# FX_HT32.net
KiCad netlist of a schematic drawn in Altium Designer
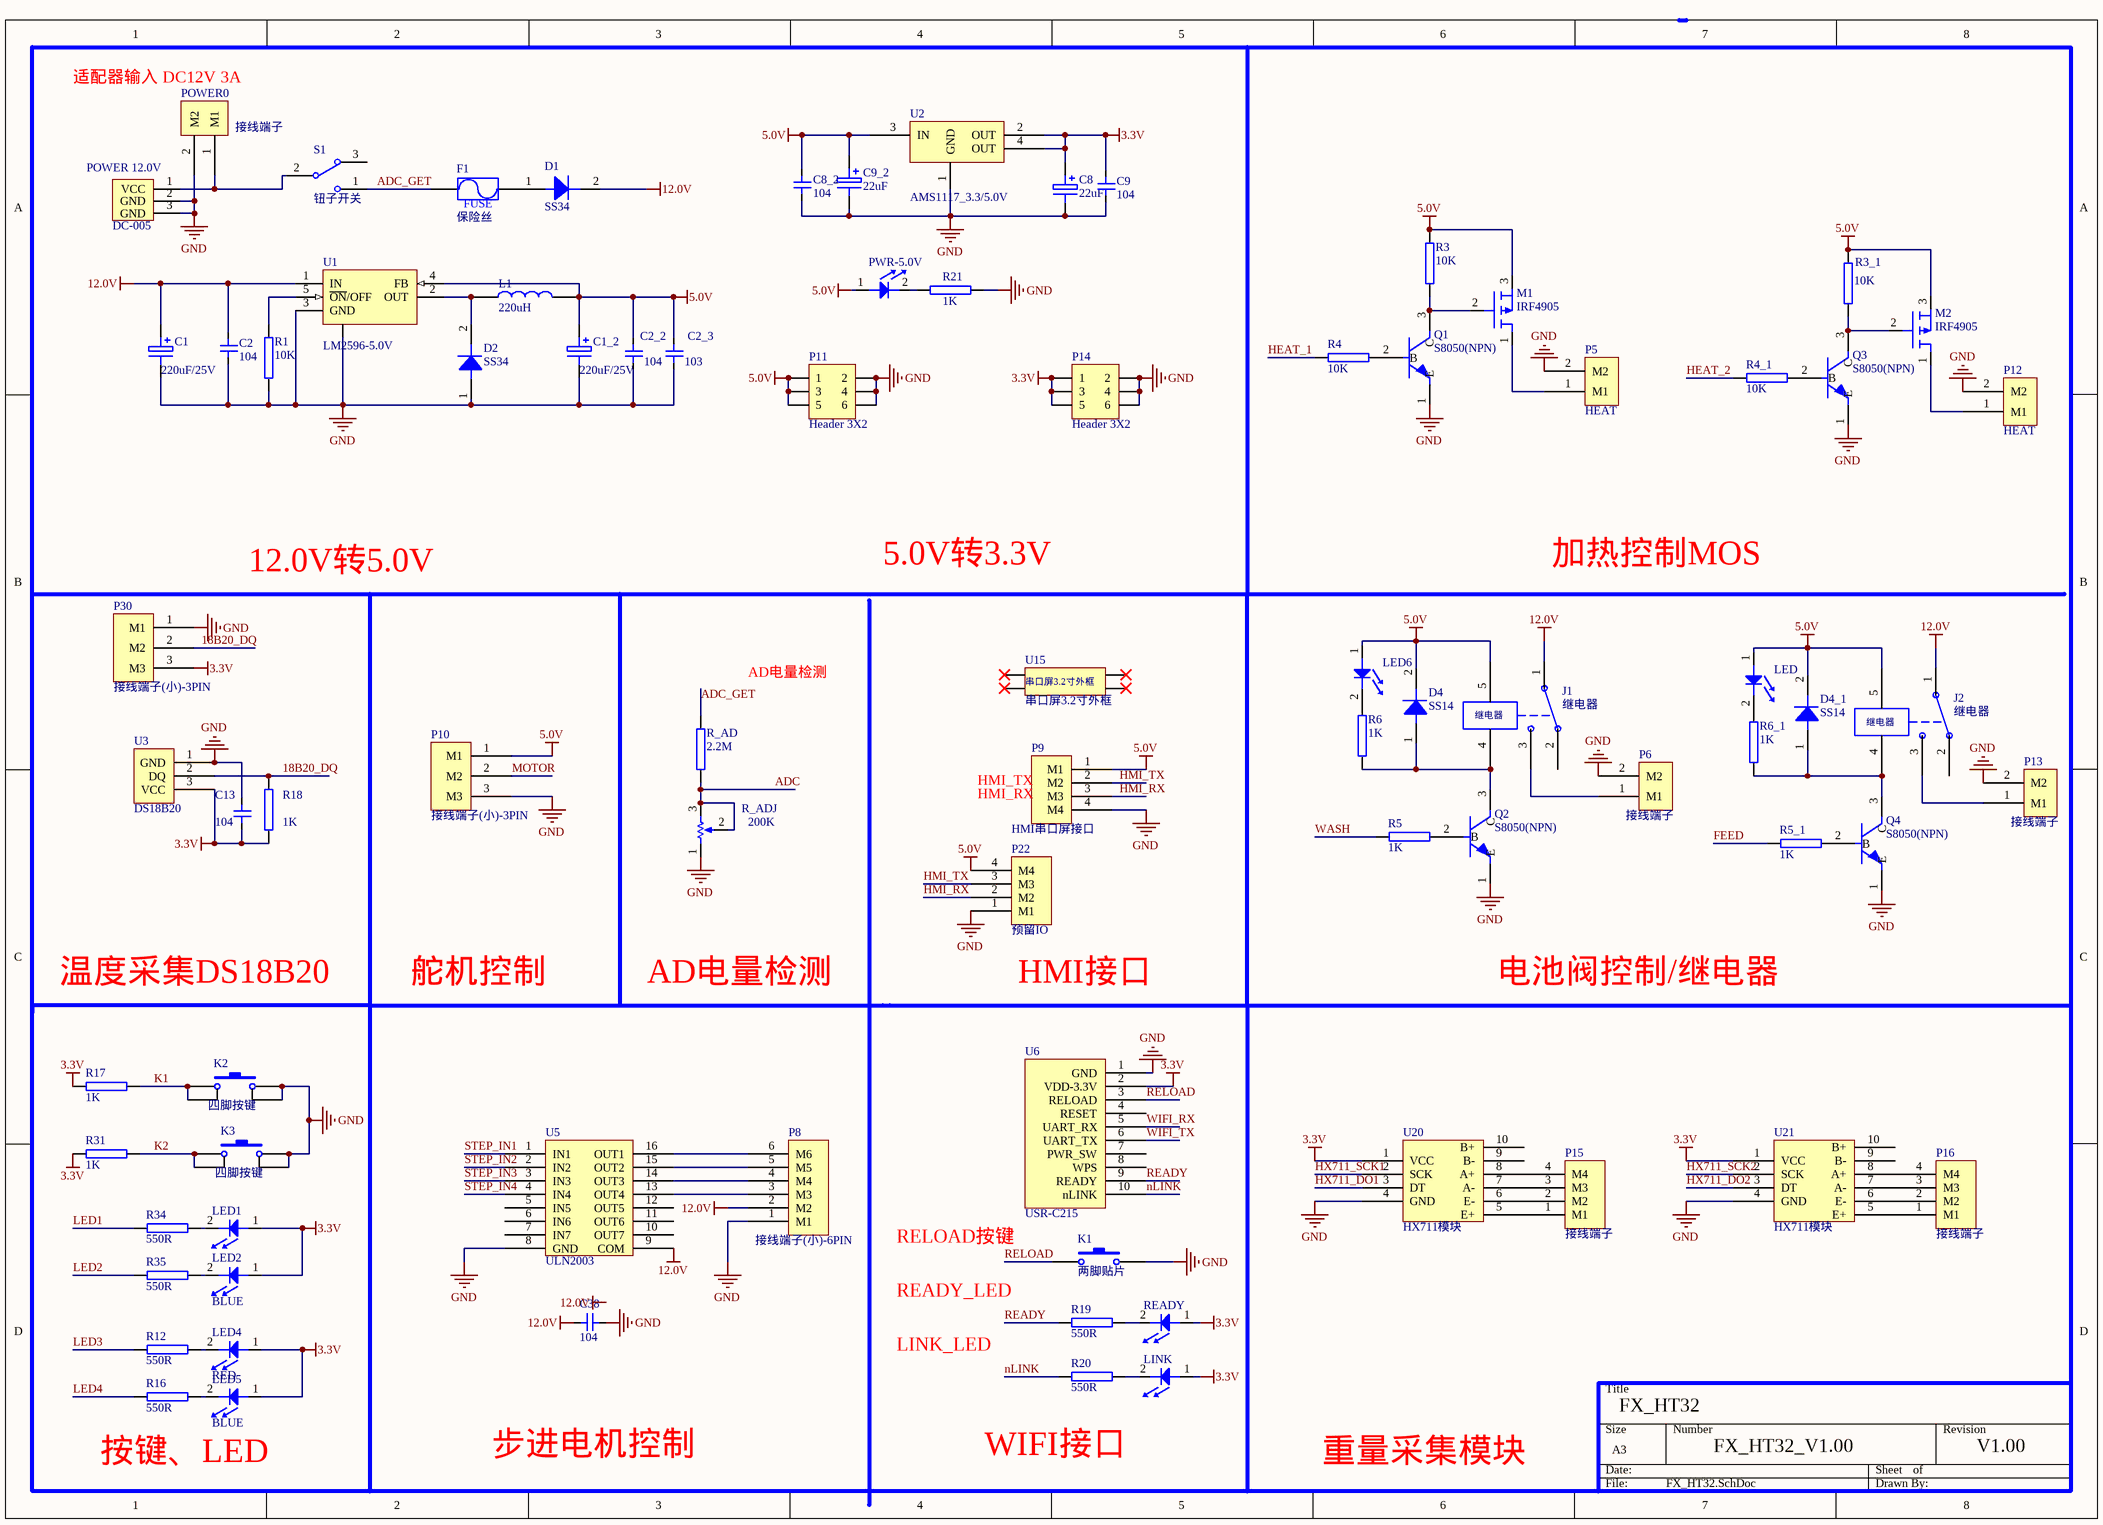
[diagram p0: FX_HT32.SchDoc]

(export (version "E")
  (design (tool "Eeschema 10.0.6"))
  (components
    (comp (ref "C1")
      (value "220uF/25V")
      (footprint "Cap1(100uF)")
      (libsource (lib "窝牛器件封装") (part "Cap1(100uF)"))
    )
    (comp (ref "C1_2")
      (value "220uF/25V")
      (footprint "Cap1(100uF)")
      (libsource (lib "窝牛器件封装") (part "Cap1(100uF)"))
    )
    (comp (ref "C2") (value "104") (footprint "0805C") (libsource (lib "窝牛器件封装") (part "C1")))
    (comp (ref "C2_2") (value "104") (footprint "0805C") (libsource (lib "窝牛器件封装") (part "C1")))
    (comp (ref "C2_3") (value "103") (footprint "0805C") (libsource (lib "窝牛器件封装") (part "C1")))
    (comp (ref "C8") (value "22uF") (footprint "Cap122uF)") (libsource (lib "窝牛器件封装") (part "Cap1(100uF)")))
    (comp (ref "C8_2") (value "104") (footprint "0805C") (libsource (lib "窝牛器件封装") (part "C1")))
    (comp (ref "C9") (value "104") (footprint "0805C") (libsource (lib "窝牛器件封装") (part "C1")))
    (comp (ref "C9_2") (value "22uF") (footprint "Cap122uF)") (libsource (lib "窝牛器件封装") (part "Cap1(100uF)")))
    (comp (ref "C13") (value "104") (footprint "0805C") (libsource (lib "窝牛器件封装") (part "C1")))
    (comp (ref "C38") (value "104") (footprint "0805C") (libsource (lib "窝牛器件封装") (part "C1")))
    (comp (ref "D1") (value "SS34") (footprint "SS14") (libsource (lib "窝牛器件封装") (part "SS14")))
    (comp (ref "D2") (value "SS34") (footprint "SS14") (libsource (lib "窝牛器件封装") (part "SS14")))
    (comp (ref "D4") (value "SS14") (footprint "SS14") (libsource (lib "窝牛器件封装") (part "SS14")))
    (comp (ref "D4_1") (value "SS14") (footprint "SS14") (libsource (lib "窝牛器件封装") (part "SS14")))
    (comp (ref "F1") (value "保险丝") (footprint "1812") (libsource (lib "窝牛器件封装") (part "F1")))
    (comp (ref "J1") (value "继电器") (footprint "继电器") (libsource (lib "窝牛器件封装") (part "继电器")))
    (comp (ref "J2") (value "继电器") (footprint "继电器") (libsource (lib "窝牛器件封装") (part "继电器")))
    (comp (ref "K1") (value "两脚贴片") (footprint "贴片按键") (libsource (lib "窝牛器件封装") (part "Key(两脚贴片)")))
    (comp (ref "K2") (value "四脚按键") (footprint "SW_PB4_DIP") (libsource (lib "窝牛器件封装") (part "Key(四脚)")))
    (comp (ref "K3") (value "四脚按键") (footprint "SW_PB4_DIP") (libsource (lib "窝牛器件封装") (part "Key(四脚)")))
    (comp (ref "L1") (value "220uH") (footprint "电感 220uh") (libsource (lib "窝牛器件封装") (part "L1")))
    (comp (ref "LED") (value "~") (footprint "0805LED") (libsource (lib "窝牛器件封装") (part "LED")))
    (comp (ref "LED1") (value "~") (footprint "0805LED") (libsource (lib "窝牛器件封装") (part "LED")))
    (comp (ref "LED2") (value "BLUE") (footprint "0805LED") (libsource (lib "窝牛器件封装") (part "LED")))
    (comp (ref "LED4") (value "RED") (footprint "0805LED") (libsource (lib "窝牛器件封装") (part "LED")))
    (comp (ref "LED5") (value "BLUE") (footprint "0805LED") (libsource (lib "窝牛器件封装") (part "LED")))
    (comp (ref "LED6") (value "~") (footprint "0805LED") (libsource (lib "窝牛器件封装") (part "LED")))
    (comp (ref "LINK") (value "~") (footprint "0805LED") (libsource (lib "") (part "LED_1")))
    (comp (ref "M1") (value "IRF4905") (footprint "IRF4905") (libsource (lib "窝牛器件封装") (part "IRF4905")))
    (comp (ref "M2") (value "IRF4905") (footprint "IRF4905") (libsource (lib "窝牛器件封装") (part "IRF4905")))
    (comp (ref "P5") (value "HEAT") (footprint "HEAT") (libsource (lib "窝牛器件封装") (part "接线端子(小)-2PIN")))
    (comp (ref "P6")
      (value "接线端子")
      (footprint "接线端子(小)-2PIN")
      (libsource (lib "窝牛器件封装") (part "接线端子(小)-2PIN"))
    )
    (comp (ref "P8")
      (value "接线端子(小)-6PIN")
      (footprint "接线端子(小)-6PIN")
      (libsource (lib "窝牛器件封装") (part "接线端子(小)-6PIN"))
    )
    (comp (ref "P9")
      (value "HMI串口屏接口")
      (footprint "接线端子(小)-4PIN")
      (libsource (lib "窝牛器件封装") (part "接线端子(小)-4PIN"))
    )
    (comp (ref "P10")
      (value "接线端子(小)-3PIN")
      (footprint "接线端子(小)-3PIN")
      (libsource (lib "窝牛器件封装") (part "接线端子(小)-3PIN"))
    )
    (comp (ref "P11")
      (value "Header 3X2")
      (footprint "Header 3X2")
      (libsource (lib "窝牛器件封装") (part "Header 3X2"))
    )
    (comp (ref "P12") (value "HEAT") (footprint "HEAT") (libsource (lib "窝牛器件封装") (part "接线端子(小)-2PIN")))
    (comp (ref "P13")
      (value "接线端子")
      (footprint "接线端子(小)-2PIN")
      (libsource (lib "窝牛器件封装") (part "接线端子(小)-2PIN"))
    )
    (comp (ref "P14")
      (value "Header 3X2")
      (footprint "Header 3X2")
      (libsource (lib "窝牛器件封装") (part "Header 3X2"))
    )
    (comp (ref "P15") (value "接线端子") (footprint "接线端子(小)-4PIN") (libsource (lib "") (part "接线端子(小)-4PIN_1")))
    (comp (ref "P16") (value "接线端子") (footprint "接线端子(小)-4PIN") (libsource (lib "") (part "接线端子(小)-4PIN_1")))
    (comp (ref "P22") (value "预留IO") (footprint "接线端子(小)-4PIN") (libsource (lib "") (part "接线端子(小)-4PIN_1")))
    (comp (ref "P30")
      (value "接线端子(小)-3PIN")
      (footprint "接线端子(小)-3PIN")
      (libsource (lib "窝牛器件封装") (part "接线端子(小)-3PIN"))
    )
    (comp (ref "POWER 12.0V")
      (value "DC-005")
      (footprint "DC-005")
      (libsource (lib "窝牛器件封装") (part "DC-005"))
    )
    (comp (ref "POWER0") (value "接线端子") (footprint "HEAT") (libsource (lib "") (part "接线端子(小)-2PIN_1")))
    (comp (ref "PWR-5.0V") (value "~") (footprint "0805LED") (libsource (lib "") (part "LED_1")))
    (comp (ref "Q1") (value "S8050(NPN)") (footprint "NPN") (libsource (lib "窝牛器件封装") (part "Q2")))
    (comp (ref "Q2") (value "S8050(NPN)") (footprint "NPN") (libsource (lib "窝牛器件封装") (part "Q2")))
    (comp (ref "Q3") (value "S8050(NPN)") (footprint "NPN") (libsource (lib "窝牛器件封装") (part "Q2")))
    (comp (ref "Q4") (value "S8050(NPN)") (footprint "NPN") (libsource (lib "窝牛器件封装") (part "Q2")))
    (comp (ref "R1") (value "10K") (footprint "0805R") (libsource (lib "窝牛器件封装") (part "R1")))
    (comp (ref "R3") (value "10K") (footprint "0805R") (libsource (lib "窝牛器件封装") (part "R1")))
    (comp (ref "R3_1") (value "10K") (footprint "0805R") (libsource (lib "窝牛器件封装") (part "R1")))
    (comp (ref "R4") (value "10K") (footprint "0805R") (libsource (lib "窝牛器件封装") (part "R1")))
    (comp (ref "R4_1") (value "10K") (footprint "0805R") (libsource (lib "窝牛器件封装") (part "R1")))
    (comp (ref "R5") (value "1K") (footprint "0805R") (libsource (lib "窝牛器件封装") (part "R1")))
    (comp (ref "R5_1") (value "1K") (footprint "0805R") (libsource (lib "窝牛器件封装") (part "R1")))
    (comp (ref "R6") (value "1K") (footprint "0805R") (libsource (lib "窝牛器件封装") (part "R1")))
    (comp (ref "R6_1") (value "1K") (footprint "0805R") (libsource (lib "窝牛器件封装") (part "R1")))
    (comp (ref "R12") (value "550R") (footprint "0805R") (libsource (lib "窝牛器件封装") (part "R1")))
    (comp (ref "R16") (value "550R") (footprint "0805R") (libsource (lib "窝牛器件封装") (part "R1")))
    (comp (ref "R17") (value "1K") (footprint "0805R") (libsource (lib "窝牛器件封装") (part "R1")))
    (comp (ref "R18") (value "1K") (footprint "0805R") (libsource (lib "窝牛器件封装") (part "R1")))
    (comp (ref "R19") (value "550R") (footprint "0805R") (libsource (lib "窝牛器件封装") (part "R1")))
    (comp (ref "R20") (value "550R") (footprint "0805R") (libsource (lib "窝牛器件封装") (part "R1")))
    (comp (ref "R21") (value "1K") (footprint "0805R") (libsource (lib "窝牛器件封装") (part "R1")))
    (comp (ref "R31") (value "1K") (footprint "0805R") (libsource (lib "窝牛器件封装") (part "R1")))
    (comp (ref "R34") (value "550R") (footprint "0805R") (libsource (lib "窝牛器件封装") (part "R1")))
    (comp (ref "R35") (value "550R") (footprint "0805R") (libsource (lib "窝牛器件封装") (part "R1")))
    (comp (ref "READY") (value "~") (footprint "0805LED") (libsource (lib "") (part "LED_1")))
    (comp (ref "R_AD") (value "2.2M") (footprint "0805R") (libsource (lib "窝牛器件封装") (part "R1")))
    (comp (ref "R_ADJ") (value "200K") (footprint "电位器") (libsource (lib "窝牛器件封装") (part "RPot")))
    (comp (ref "S1") (value "钮子开关") (footprint "钮子开关(大)") (libsource (lib "窝牛器件封装") (part "钮子开关")))
    (comp (ref "U1") (value "LM2596-5.0V") (footprint "TO-263-5") (libsource (lib "窝牛器件封装") (part "LM2596")))
    (comp (ref "U2")
      (value "AMS1117_3.3/5.0V")
      (footprint "SOT-223")
      (libsource (lib "窝牛器件封装") (part "AMS1117-3.3V/5.0V"))
    )
    (comp (ref "U3") (value "DS18B20") (footprint "DS18B20") (libsource (lib "窝牛器件封装") (part "DS18B20")))
    (comp (ref "U5") (value "ULN2003") (footprint "ULN2003") (libsource (lib "窝牛器件封装") (part "ULN2003")))
    (comp (ref "U6") (value "USR-C215") (footprint "USR-C215") (libsource (lib "窝牛器件封装") (part "USR-C215")))
    (comp (ref "U15") (value "串口屏3.2寸外框") (footprint "串口屏 3.2寸") (libsource (lib "窝牛器件封装") (part "串口屏3.2寸")))
    (comp (ref "U20") (value "HX711模块") (footprint "HX711模块") (libsource (lib "窝牛器件封装") (part "HX711模块")))
    (comp (ref "U21") (value "HX711模块") (footprint "HX711模块") (libsource (lib "窝牛器件封装") (part "HX711模块")))
  )
  (nets
    (net (code "1") (name "/18B20_DQ") (class "Default")
      (node (ref "P30") (pin "2") (pinfunction "M2_2") (pintype "passive"))
      (node (ref "R18") (pin "1") (pinfunction "1_1") (pintype "passive"))
      (node (ref "U3") (pin "2") (pinfunction "DQ_2") (pintype "passive"))
    )
    (net (code "2") (name "/ADC") (class "Default")
      (node (ref "R_AD") (pin "2") (pinfunction "2_2") (pintype "passive"))
      (node (ref "R_ADJ") (pin "2") (pinfunction "TAP_2") (pintype "passive"))
      (node (ref "R_ADJ") (pin "3") (pinfunction "BOT_3") (pintype "passive"))
    )
    (net (code "3") (name "/ADC_GET") (class "Default")
      (node (ref "F1") (pin "1") (pinfunction "1_1") (pintype "passive"))
      (node (ref "R_AD") (pin "1") (pinfunction "1_1") (pintype "passive"))
      (node (ref "S1") (pin "1") (pinfunction "1_1") (pintype "passive"))
    )
    (net (code "4") (name "/FEED") (class "Default")
      (node (ref "R5_1") (pin "1") (pinfunction "1_1") (pintype "passive"))
    )
    (net (code "5") (name "/HEAT_1") (class "Default")
      (node (ref "R4") (pin "1") (pinfunction "1_1") (pintype "passive"))
    )
    (net (code "6") (name "/HEAT_2") (class "Default")
      (node (ref "R4_1") (pin "1") (pinfunction "1_1") (pintype "passive"))
    )
    (net (code "7") (name "/HMI_RX") (class "Default")
      (node (ref "P22") (pin "2") (pinfunction "M2_2") (pintype "passive"))
      (node (ref "P9") (pin "3") (pinfunction "M3_3") (pintype "passive"))
    )
    (net (code "8") (name "/HMI_TX") (class "Default")
      (node (ref "P22") (pin "3") (pinfunction "M3_3") (pintype "passive"))
      (node (ref "P9") (pin "2") (pinfunction "M2_2") (pintype "passive"))
    )
    (net (code "9") (name "/HX711_DO1") (class "Default")
      (node (ref "U20") (pin "3") (pinfunction "DT_3") (pintype "passive"))
    )
    (net (code "10") (name "/HX711_DO2") (class "Default")
      (node (ref "U21") (pin "3") (pinfunction "DT_3") (pintype "passive"))
    )
    (net (code "11") (name "/HX711_SCK1") (class "Default")
      (node (ref "U20") (pin "2") (pinfunction "SCK_2") (pintype "passive"))
    )
    (net (code "12") (name "/HX711_SCK2") (class "Default")
      (node (ref "U21") (pin "2") (pinfunction "SCK_2") (pintype "passive"))
    )
    (net (code "13") (name "/K1") (class "Default")
      (node (ref "K2") (pin "1") (pinfunction "1_1") (pintype "passive"))
      (node (ref "K2") (pin "4") (pinfunction "4_4") (pintype "passive"))
      (node (ref "R17") (pin "2") (pinfunction "2_2") (pintype "passive"))
    )
    (net (code "14") (name "/K2") (class "Default")
      (node (ref "K3") (pin "1") (pinfunction "1_1") (pintype "passive"))
      (node (ref "K3") (pin "4") (pinfunction "4_4") (pintype "passive"))
      (node (ref "R31") (pin "2") (pinfunction "2_2") (pintype "passive"))
    )
    (net (code "15") (name "/LED1") (class "Default")
      (node (ref "R34") (pin "1") (pinfunction "1_1") (pintype "passive"))
    )
    (net (code "16") (name "/LED2") (class "Default")
      (node (ref "R35") (pin "1") (pinfunction "1_1") (pintype "passive"))
    )
    (net (code "17") (name "/LED3") (class "Default")
      (node (ref "R12") (pin "1") (pinfunction "1_1") (pintype "passive"))
    )
    (net (code "18") (name "/LED4") (class "Default")
      (node (ref "R16") (pin "1") (pinfunction "1_1") (pintype "passive"))
    )
    (net (code "19") (name "/MOTOR") (class "Default")
      (node (ref "P10") (pin "2") (pinfunction "M2_2") (pintype "passive"))
    )
    (net (code "20") (name "/READY") (class "Default")
      (node (ref "R19") (pin "1") (pinfunction "1_1") (pintype "passive"))
      (node (ref "U6") (pin "9") (pinfunction "READY_9") (pintype "passive"))
    )
    (net (code "21") (name "/RELOAD") (class "Default")
      (node (ref "K1") (pin "1") (pinfunction "1_1") (pintype "passive"))
      (node (ref "U6") (pin "3") (pinfunction "RELOAD_3") (pintype "passive"))
    )
    (net (code "22") (name "/STEP_IN1") (class "Default")
      (node (ref "U5") (pin "1") (pinfunction "IN1_1") (pintype "passive"))
    )
    (net (code "23") (name "/STEP_IN2") (class "Default")
      (node (ref "U5") (pin "2") (pinfunction "IN2_2") (pintype "passive"))
    )
    (net (code "24") (name "/STEP_IN3") (class "Default")
      (node (ref "U5") (pin "3") (pinfunction "IN3_3") (pintype "passive"))
    )
    (net (code "25") (name "/STEP_IN4") (class "Default")
      (node (ref "U5") (pin "4") (pinfunction "IN4_4") (pintype "passive"))
    )
    (net (code "26") (name "/WASH") (class "Default")
      (node (ref "R5") (pin "1") (pinfunction "1_1") (pintype "passive"))
    )
    (net (code "27") (name "/WIFI_RX") (class "Default")
      (node (ref "U6") (pin "5") (pinfunction "UART_RX_5") (pintype "passive"))
    )
    (net (code "28") (name "/WIFI_TX") (class "Default")
      (node (ref "U6") (pin "6") (pinfunction "UART_TX_6") (pintype "passive"))
    )
    (net (code "29") (name "/nLINK") (class "Default")
      (node (ref "R20") (pin "1") (pinfunction "1_1") (pintype "passive"))
      (node (ref "U6") (pin "10") (pinfunction "nLINK_10") (pintype "passive"))
    )
    (net (code "30") (name "3.3V") (class "Default")
      (node (ref "C13") (pin "1") (pinfunction "1_1") (pintype "passive"))
      (node (ref "C8") (pin "1") (pinfunction "1_1") (pintype "passive"))
      (node (ref "C9") (pin "2") (pinfunction "2_2") (pintype "passive"))
      (node (ref "LED1") (pin "1") (pinfunction "1_1") (pintype "passive"))
      (node (ref "LED2") (pin "1") (pinfunction "1_1") (pintype "passive"))
      (node (ref "LED4") (pin "1") (pinfunction "1_1") (pintype "passive"))
      (node (ref "LED5") (pin "1") (pinfunction "1_1") (pintype "passive"))
      (node (ref "LINK") (pin "1") (pinfunction "1_1") (pintype "passive"))
      (node (ref "P14") (pin "1") (pinfunction "1_1") (pintype "passive"))
      (node (ref "P14") (pin "3") (pinfunction "3_3") (pintype "passive"))
      (node (ref "P14") (pin "5") (pinfunction "5_5") (pintype "passive"))
      (node (ref "P30") (pin "3") (pinfunction "M3_3") (pintype "passive"))
      (node (ref "R17") (pin "1") (pinfunction "1_1") (pintype "passive"))
      (node (ref "R18") (pin "2") (pinfunction "2_2") (pintype "passive"))
      (node (ref "R31") (pin "1") (pinfunction "1_1") (pintype "passive"))
      (node (ref "READY") (pin "1") (pinfunction "1_1") (pintype "passive"))
      (node (ref "U2") (pin "2") (pinfunction "OUT_2") (pintype "passive"))
      (node (ref "U2") (pin "4") (pinfunction "OUT_4") (pintype "passive"))
      (node (ref "U20") (pin "1") (pinfunction "VCC_1") (pintype "passive"))
      (node (ref "U21") (pin "1") (pinfunction "VCC_1") (pintype "passive"))
      (node (ref "U3") (pin "3") (pinfunction "VCC_3") (pintype "passive"))
      (node (ref "U6") (pin "2") (pinfunction "VDD-3.3V_2") (pintype "passive"))
    )
    (net (code "31") (name "5.0V") (class "Default")
      (node (ref "C1_2") (pin "1") (pinfunction "1_1") (pintype "passive"))
      (node (ref "C2_2") (pin "2") (pinfunction "2_2") (pintype "passive"))
      (node (ref "C2_3") (pin "2") (pinfunction "2_2") (pintype "passive"))
      (node (ref "C8_2") (pin "2") (pinfunction "2_2") (pintype "passive"))
      (node (ref "C9_2") (pin "1") (pinfunction "1_1") (pintype "passive"))
      (node (ref "D4") (pin "2") (pinfunction "2_2") (pintype "passive"))
      (node (ref "D4_1") (pin "2") (pinfunction "2_2") (pintype "passive"))
      (node (ref "J1") (pin "5") (pinfunction "5_5") (pintype "passive"))
      (node (ref "J2") (pin "5") (pinfunction "5_5") (pintype "passive"))
      (node (ref "L1") (pin "2") (pinfunction "2_2") (pintype "passive"))
      (node (ref "LED") (pin "1") (pinfunction "1_1") (pintype "passive"))
      (node (ref "LED6") (pin "1") (pinfunction "1_1") (pintype "passive"))
      (node (ref "M1") (pin "3") (pinfunction "3_3") (pintype "passive"))
      (node (ref "M2") (pin "3") (pinfunction "3_3") (pintype "passive"))
      (node (ref "P10") (pin "1") (pinfunction "M1_1") (pintype "passive"))
      (node (ref "P11") (pin "1") (pinfunction "1_1") (pintype "passive"))
      (node (ref "P11") (pin "3") (pinfunction "3_3") (pintype "passive"))
      (node (ref "P11") (pin "5") (pinfunction "5_5") (pintype "passive"))
      (node (ref "P22") (pin "4") (pinfunction "M4_4") (pintype "passive"))
      (node (ref "P9") (pin "1") (pinfunction "M1_1") (pintype "passive"))
      (node (ref "PWR-5.0V") (pin "1") (pinfunction "1_1") (pintype "passive"))
      (node (ref "R3") (pin "2") (pinfunction "2_2") (pintype "passive"))
      (node (ref "R3_1") (pin "2") (pinfunction "2_2") (pintype "passive"))
      (node (ref "U1") (pin "4") (pinfunction "FB_4") (pintype "input"))
      (node (ref "U2") (pin "3") (pinfunction "IN_3") (pintype "passive"))
    )
    (net (code "32") (name "12.0V") (class "Default")
      (node (ref "C1") (pin "1") (pinfunction "1_1") (pintype "passive"))
      (node (ref "C2") (pin "2") (pinfunction "2_2") (pintype "passive"))
      (node (ref "C38") (pin "2") (pinfunction "2_2") (pintype "passive"))
      (node (ref "D1") (pin "2") (pinfunction "2_2") (pintype "passive"))
      (node (ref "J1") (pin "1") (pinfunction "1_1") (pintype "passive"))
      (node (ref "J2") (pin "1") (pinfunction "1_1") (pintype "passive"))
      (node (ref "P8") (pin "2") (pinfunction "M2_2") (pintype "passive"))
      (node (ref "U1") (pin "1") (pinfunction "IN_1") (pintype "power_in"))
      (node (ref "U5") (pin "9") (pinfunction "COM_9") (pintype "passive"))
    )
    (net (code "33") (name "GND") (class "Default")
      (node (ref "C1") (pin "2") (pinfunction "2_2") (pintype "passive"))
      (node (ref "C13") (pin "2") (pinfunction "2_2") (pintype "passive"))
      (node (ref "C1_2") (pin "2") (pinfunction "2_2") (pintype "passive"))
      (node (ref "C2") (pin "1") (pinfunction "1_1") (pintype "passive"))
      (node (ref "C2_2") (pin "1") (pinfunction "1_1") (pintype "passive"))
      (node (ref "C2_3") (pin "1") (pinfunction "1_1") (pintype "passive"))
      (node (ref "C38") (pin "1") (pinfunction "1_1") (pintype "passive"))
      (node (ref "C8") (pin "2") (pinfunction "2_2") (pintype "passive"))
      (node (ref "C8_2") (pin "1") (pinfunction "1_1") (pintype "passive"))
      (node (ref "C9") (pin "1") (pinfunction "1_1") (pintype "passive"))
      (node (ref "C9_2") (pin "2") (pinfunction "2_2") (pintype "passive"))
      (node (ref "D2") (pin "1") (pintype "passive"))
      (node (ref "K1") (pin "2") (pinfunction "2_2") (pintype "passive"))
      (node (ref "K2") (pin "2") (pinfunction "2_2") (pintype "passive"))
      (node (ref "K2") (pin "3") (pinfunction "3_3") (pintype "passive"))
      (node (ref "K3") (pin "2") (pinfunction "2_2") (pintype "passive"))
      (node (ref "K3") (pin "3") (pinfunction "3_3") (pintype "passive"))
      (node (ref "P10") (pin "3") (pinfunction "M3_3") (pintype "passive"))
      (node (ref "P11") (pin "2") (pinfunction "2_2") (pintype "passive"))
      (node (ref "P11") (pin "4") (pinfunction "4_4") (pintype "passive"))
      (node (ref "P11") (pin "6") (pinfunction "6_6") (pintype "passive"))
      (node (ref "P12") (pin "2") (pinfunction "M2_2") (pintype "passive"))
      (node (ref "P13") (pin "2") (pinfunction "M2_2") (pintype "passive"))
      (node (ref "P14") (pin "2") (pinfunction "2_2") (pintype "passive"))
      (node (ref "P14") (pin "4") (pinfunction "4_4") (pintype "passive"))
      (node (ref "P14") (pin "6") (pinfunction "6_6") (pintype "passive"))
      (node (ref "P22") (pin "1") (pinfunction "M1_1") (pintype "passive"))
      (node (ref "P30") (pin "1") (pinfunction "M1_1") (pintype "passive"))
      (node (ref "P5") (pin "2") (pinfunction "M2_2") (pintype "passive"))
      (node (ref "P6") (pin "2") (pinfunction "M2_2") (pintype "passive"))
      (node (ref "P8") (pin "1") (pinfunction "M1_1") (pintype "passive"))
      (node (ref "P9") (pin "4") (pinfunction "M4_4") (pintype "passive"))
      (node (ref "POWER 12.0V") (pin "2") (pinfunction "GND_2") (pintype "passive"))
      (node (ref "POWER 12.0V") (pin "3") (pinfunction "GND_3") (pintype "passive"))
      (node (ref "POWER0") (pin "2") (pinfunction "M2_2") (pintype "passive"))
      (node (ref "Q1") (pin "1") (pinfunction "E_1") (pintype "passive"))
      (node (ref "Q2") (pin "1") (pinfunction "E_1") (pintype "passive"))
      (node (ref "Q3") (pin "1") (pinfunction "E_1") (pintype "passive"))
      (node (ref "Q4") (pin "1") (pinfunction "E_1") (pintype "passive"))
      (node (ref "R1") (pin "1") (pinfunction "1_1") (pintype "passive"))
      (node (ref "R21") (pin "2") (pinfunction "2_2") (pintype "passive"))
      (node (ref "R_ADJ") (pin "1") (pinfunction "TOP_1") (pintype "passive"))
      (node (ref "U1") (pin "3") (pinfunction "GND_3") (pintype "power_in"))
      (node (ref "U1") (pin "6") (pinfunction "6_6") (pintype "power_in"))
      (node (ref "U2") (pin "1") (pinfunction "GND_1") (pintype "passive"))
      (node (ref "U20") (pin "4") (pinfunction "GND_4") (pintype "passive"))
      (node (ref "U21") (pin "4") (pinfunction "GND_4") (pintype "passive"))
      (node (ref "U3") (pin "1") (pinfunction "GND_1") (pintype "passive"))
      (node (ref "U5") (pin "8") (pinfunction "GND_8") (pintype "passive"))
      (node (ref "U6") (pin "1") (pinfunction "GND_1") (pintype "passive"))
    )
    (net (code "34") (name "Net-(D1-Pad1)") (class "Default")
      (node (ref "D1") (pin "1") (pintype "passive"))
      (node (ref "F1") (pin "2") (pinfunction "2_2") (pintype "passive"))
    )
    (net (code "35") (name "Net-(LED-Pad2)") (class "Default")
      (node (ref "LED") (pin "2") (pinfunction "2_2") (pintype "passive"))
      (node (ref "R6_1") (pin "1") (pinfunction "1_1") (pintype "passive"))
    )
    (net (code "36") (name "Net-(LED1-Pad2)") (class "Default")
      (node (ref "LED1") (pin "2") (pinfunction "2_2") (pintype "passive"))
      (node (ref "R34") (pin "2") (pinfunction "2_2") (pintype "passive"))
    )
    (net (code "37") (name "Net-(LED2-Pad2)") (class "Default")
      (node (ref "LED2") (pin "2") (pinfunction "2_2") (pintype "passive"))
      (node (ref "R35") (pin "2") (pinfunction "2_2") (pintype "passive"))
    )
    (net (code "38") (name "Net-(LED4-Pad2)") (class "Default")
      (node (ref "LED4") (pin "2") (pinfunction "2_2") (pintype "passive"))
      (node (ref "R12") (pin "2") (pinfunction "2_2") (pintype "passive"))
    )
    (net (code "39") (name "Net-(LED5-Pad2)") (class "Default")
      (node (ref "LED5") (pin "2") (pinfunction "2_2") (pintype "passive"))
      (node (ref "R16") (pin "2") (pinfunction "2_2") (pintype "passive"))
    )
    (net (code "40") (name "Net-(LED6-Pad2)") (class "Default")
      (node (ref "LED6") (pin "2") (pinfunction "2_2") (pintype "passive"))
      (node (ref "R6") (pin "1") (pinfunction "1_1") (pintype "passive"))
    )
    (net (code "41") (name "Net-(LINK-Pad2)") (class "Default")
      (node (ref "LINK") (pin "2") (pinfunction "2_2") (pintype "passive"))
      (node (ref "R20") (pin "2") (pinfunction "2_2") (pintype "passive"))
    )
    (net (code "42") (name "Net-(P5-M1)") (class "Default")
      (node (ref "M1") (pin "1") (pinfunction "1_1") (pintype "passive"))
      (node (ref "P5") (pin "1") (pinfunction "M1_1") (pintype "passive"))
    )
    (net (code "43") (name "Net-(P6-M1)") (class "Default")
      (node (ref "J1") (pin "3") (pinfunction "3_3") (pintype "passive"))
      (node (ref "P6") (pin "1") (pinfunction "M1_1") (pintype "passive"))
    )
    (net (code "44") (name "Net-(P8-M3)") (class "Default")
      (node (ref "P8") (pin "3") (pinfunction "M3_3") (pintype "passive"))
      (node (ref "U5") (pin "13") (pinfunction "OUT4_13") (pintype "passive"))
    )
    (net (code "45") (name "Net-(P8-M4)") (class "Default")
      (node (ref "P8") (pin "4") (pinfunction "M4_4") (pintype "passive"))
      (node (ref "U5") (pin "14") (pinfunction "OUT3_14") (pintype "passive"))
    )
    (net (code "46") (name "Net-(P8-M5)") (class "Default")
      (node (ref "P8") (pin "5") (pinfunction "M5_5") (pintype "passive"))
      (node (ref "U5") (pin "15") (pinfunction "OUT2_15") (pintype "passive"))
    )
    (net (code "47") (name "Net-(P8-M6)") (class "Default")
      (node (ref "P8") (pin "6") (pinfunction "M6_6") (pintype "passive"))
      (node (ref "U5") (pin "16") (pinfunction "OUT1_16") (pintype "passive"))
    )
    (net (code "48") (name "Net-(P12-M1)") (class "Default")
      (node (ref "M2") (pin "1") (pinfunction "1_1") (pintype "passive"))
      (node (ref "P12") (pin "1") (pinfunction "M1_1") (pintype "passive"))
    )
    (net (code "49") (name "Net-(P13-M1)") (class "Default")
      (node (ref "J2") (pin "3") (pinfunction "3_3") (pintype "passive"))
      (node (ref "P13") (pin "1") (pinfunction "M1_1") (pintype "passive"))
    )
    (net (code "50") (name "Net-(P15-M1)") (class "Default")
      (node (ref "P15") (pin "1") (pinfunction "M1_1") (pintype "passive"))
      (node (ref "U20") (pin "5") (pinfunction "E+_5") (pintype "passive"))
    )
    (net (code "51") (name "Net-(P15-M2)") (class "Default")
      (node (ref "P15") (pin "2") (pinfunction "M2_2") (pintype "passive"))
      (node (ref "U20") (pin "6") (pinfunction "E-_6") (pintype "passive"))
    )
    (net (code "52") (name "Net-(P15-M3)") (class "Default")
      (node (ref "P15") (pin "3") (pinfunction "M3_3") (pintype "passive"))
      (node (ref "U20") (pin "7") (pinfunction "A-_7") (pintype "passive"))
    )
    (net (code "53") (name "Net-(P15-M4)") (class "Default")
      (node (ref "P15") (pin "4") (pinfunction "M4_4") (pintype "passive"))
      (node (ref "U20") (pin "8") (pinfunction "A+_8") (pintype "passive"))
    )
    (net (code "54") (name "Net-(P16-M1)") (class "Default")
      (node (ref "P16") (pin "1") (pinfunction "M1_1") (pintype "passive"))
      (node (ref "U21") (pin "5") (pinfunction "E+_5") (pintype "passive"))
    )
    (net (code "55") (name "Net-(P16-M2)") (class "Default")
      (node (ref "P16") (pin "2") (pinfunction "M2_2") (pintype "passive"))
      (node (ref "U21") (pin "6") (pinfunction "E-_6") (pintype "passive"))
    )
    (net (code "56") (name "Net-(P16-M3)") (class "Default")
      (node (ref "P16") (pin "3") (pinfunction "M3_3") (pintype "passive"))
      (node (ref "U21") (pin "7") (pinfunction "A-_7") (pintype "passive"))
    )
    (net (code "57") (name "Net-(P16-M4)") (class "Default")
      (node (ref "P16") (pin "4") (pinfunction "M4_4") (pintype "passive"))
      (node (ref "U21") (pin "8") (pinfunction "A+_8") (pintype "passive"))
    )
    (net (code "58") (name "Net-(POWER 12.0V-VCC)") (class "Default")
      (node (ref "POWER 12.0V") (pin "1") (pinfunction "VCC_1") (pintype "passive"))
      (node (ref "POWER0") (pin "1") (pinfunction "M1_1") (pintype "passive"))
      (node (ref "S1") (pin "2") (pinfunction "2_2") (pintype "passive"))
    )
    (net (code "59") (name "Net-(PWR-5.0V-Pad2)") (class "Default")
      (node (ref "PWR-5.0V") (pin "2") (pinfunction "2_2") (pintype "passive"))
      (node (ref "R21") (pin "1") (pinfunction "1_1") (pintype "passive"))
    )
    (net (code "60") (name "Net-(Q1-B)") (class "Default")
      (node (ref "Q1") (pin "2") (pinfunction "B_2") (pintype "passive"))
      (node (ref "R4") (pin "2") (pinfunction "2_2") (pintype "passive"))
    )
    (net (code "61") (name "Net-(Q1-C)") (class "Default")
      (node (ref "M1") (pin "2") (pinfunction "2_2") (pintype "passive"))
      (node (ref "Q1") (pin "3") (pinfunction "C_3") (pintype "passive"))
      (node (ref "R3") (pin "1") (pinfunction "1_1") (pintype "passive"))
    )
    (net (code "62") (name "Net-(Q2-B)") (class "Default")
      (node (ref "Q2") (pin "2") (pinfunction "B_2") (pintype "passive"))
      (node (ref "R5") (pin "2") (pinfunction "2_2") (pintype "passive"))
    )
    (net (code "63") (name "Net-(Q2-C)") (class "Default")
      (node (ref "D4") (pin "1") (pintype "passive"))
      (node (ref "J1") (pin "4") (pinfunction "4_4") (pintype "passive"))
      (node (ref "Q2") (pin "3") (pinfunction "C_3") (pintype "passive"))
      (node (ref "R6") (pin "2") (pinfunction "2_2") (pintype "passive"))
    )
    (net (code "64") (name "Net-(Q3-B)") (class "Default")
      (node (ref "Q3") (pin "2") (pinfunction "B_2") (pintype "passive"))
      (node (ref "R4_1") (pin "2") (pinfunction "2_2") (pintype "passive"))
    )
    (net (code "65") (name "Net-(Q3-C)") (class "Default")
      (node (ref "M2") (pin "2") (pinfunction "2_2") (pintype "passive"))
      (node (ref "Q3") (pin "3") (pinfunction "C_3") (pintype "passive"))
      (node (ref "R3_1") (pin "1") (pinfunction "1_1") (pintype "passive"))
    )
    (net (code "66") (name "Net-(Q4-B)") (class "Default")
      (node (ref "Q4") (pin "2") (pinfunction "B_2") (pintype "passive"))
      (node (ref "R5_1") (pin "2") (pinfunction "2_2") (pintype "passive"))
    )
    (net (code "67") (name "Net-(Q4-C)") (class "Default")
      (node (ref "D4_1") (pin "1") (pintype "passive"))
      (node (ref "J2") (pin "4") (pinfunction "4_4") (pintype "passive"))
      (node (ref "Q4") (pin "3") (pinfunction "C_3") (pintype "passive"))
      (node (ref "R6_1") (pin "2") (pinfunction "2_2") (pintype "passive"))
    )
    (net (code "68") (name "Net-(R19-Pad2)") (class "Default")
      (node (ref "R19") (pin "2") (pinfunction "2_2") (pintype "passive"))
      (node (ref "READY") (pin "2") (pinfunction "2_2") (pintype "passive"))
    )
    (net (code "69") (name "Net-(U1-OUT)") (class "Default")
      (node (ref "D2") (pin "2") (pinfunction "2_2") (pintype "passive"))
      (node (ref "L1") (pin "1") (pinfunction "1_1") (pintype "passive"))
      (node (ref "U1") (pin "2") (pinfunction "OUT_2") (pintype "power_in"))
    )
    (net (code "70") (name "Net-(U1-~{ON}{slash}OFF)") (class "Default")
      (node (ref "R1") (pin "2") (pinfunction "2_2") (pintype "passive"))
      (node (ref "U1") (pin "5") (pinfunction "~{ON}/OFF_5") (pintype "input"))
    )
    (net (code "71") (name "unconnected-(J1-Pad2)") (class "Default")
      (node (ref "J1") (pin "2") (pinfunction "2_2") (pintype "passive"))
    )
    (net (code "72") (name "unconnected-(J2-Pad2)") (class "Default")
      (node (ref "J2") (pin "2") (pinfunction "2_2") (pintype "passive"))
    )
    (net (code "73") (name "unconnected-(S1-Pad3)") (class "Default")
      (node (ref "S1") (pin "3") (pinfunction "3_3") (pintype "passive"))
    )
    (net (code "74") (name "unconnected-(U5-IN5-Pad5)") (class "Default")
      (node (ref "U5") (pin "5") (pinfunction "IN5_5") (pintype "passive"))
    )
    (net (code "75") (name "unconnected-(U5-IN6-Pad6)") (class "Default")
      (node (ref "U5") (pin "6") (pinfunction "IN6_6") (pintype "passive"))
    )
    (net (code "76") (name "unconnected-(U5-IN7-Pad7)") (class "Default")
      (node (ref "U5") (pin "7") (pinfunction "IN7_7") (pintype "passive"))
    )
    (net (code "77") (name "unconnected-(U5-OUT5-Pad12)") (class "Default")
      (node (ref "U5") (pin "12") (pinfunction "OUT5_12") (pintype "passive"))
    )
    (net (code "78") (name "unconnected-(U5-OUT6-Pad11)") (class "Default")
      (node (ref "U5") (pin "11") (pinfunction "OUT6_11") (pintype "passive"))
    )
    (net (code "79") (name "unconnected-(U5-OUT7-Pad10)") (class "Default")
      (node (ref "U5") (pin "10") (pinfunction "OUT7_10") (pintype "passive"))
    )
    (net (code "80") (name "unconnected-(U6-PWR_SW-Pad7)") (class "Default")
      (node (ref "U6") (pin "7") (pinfunction "PWR_SW_7") (pintype "passive"))
    )
    (net (code "81") (name "unconnected-(U6-RESET-Pad4)") (class "Default")
      (node (ref "U6") (pin "4") (pinfunction "RESET_4") (pintype "passive"))
    )
    (net (code "82") (name "unconnected-(U6-WPS-Pad8)") (class "Default")
      (node (ref "U6") (pin "8") (pinfunction "WPS_8") (pintype "passive"))
    )
    (net (code "83") (name "unconnected-(U15-Pad0)") (class "Default")
      (node (ref "U15") (pin "0") (pinfunction "0_0") (pintype "passive"))
    )
    (net (code "84") (name "unconnected-(U15-Pad0)") (class "Default")
      (node (ref "U15") (pin "0") (pinfunction "0_0") (pintype "passive+no_connect"))
    )
    (net (code "85") (name "unconnected-(U15-Pad0)_1") (class "Default")
      (node (ref "U15") (pin "0") (pinfunction "0_0") (pintype "passive+no_connect"))
    )
    (net (code "86") (name "unconnected-(U15-Pad0)_2") (class "Default")
      (node (ref "U15") (pin "0") (pinfunction "0_0") (pintype "passive+no_connect"))
    )
    (net (code "87") (name "unconnected-(U20-B+-Pad10)") (class "Default")
      (node (ref "U20") (pin "10") (pinfunction "B+_10") (pintype "passive"))
    )
    (net (code "88") (name "unconnected-(U20-B--Pad9)") (class "Default")
      (node (ref "U20") (pin "9") (pinfunction "B-_9") (pintype "passive"))
    )
    (net (code "89") (name "unconnected-(U21-B+-Pad10)") (class "Default")
      (node (ref "U21") (pin "10") (pinfunction "B+_10") (pintype "passive"))
    )
    (net (code "90") (name "unconnected-(U21-B--Pad9)") (class "Default")
      (node (ref "U21") (pin "9") (pinfunction "B-_9") (pintype "passive"))
    )
  )
)
